# 03_-_Converter.net
KiCad netlist of a schematic drawn in Altium Designer
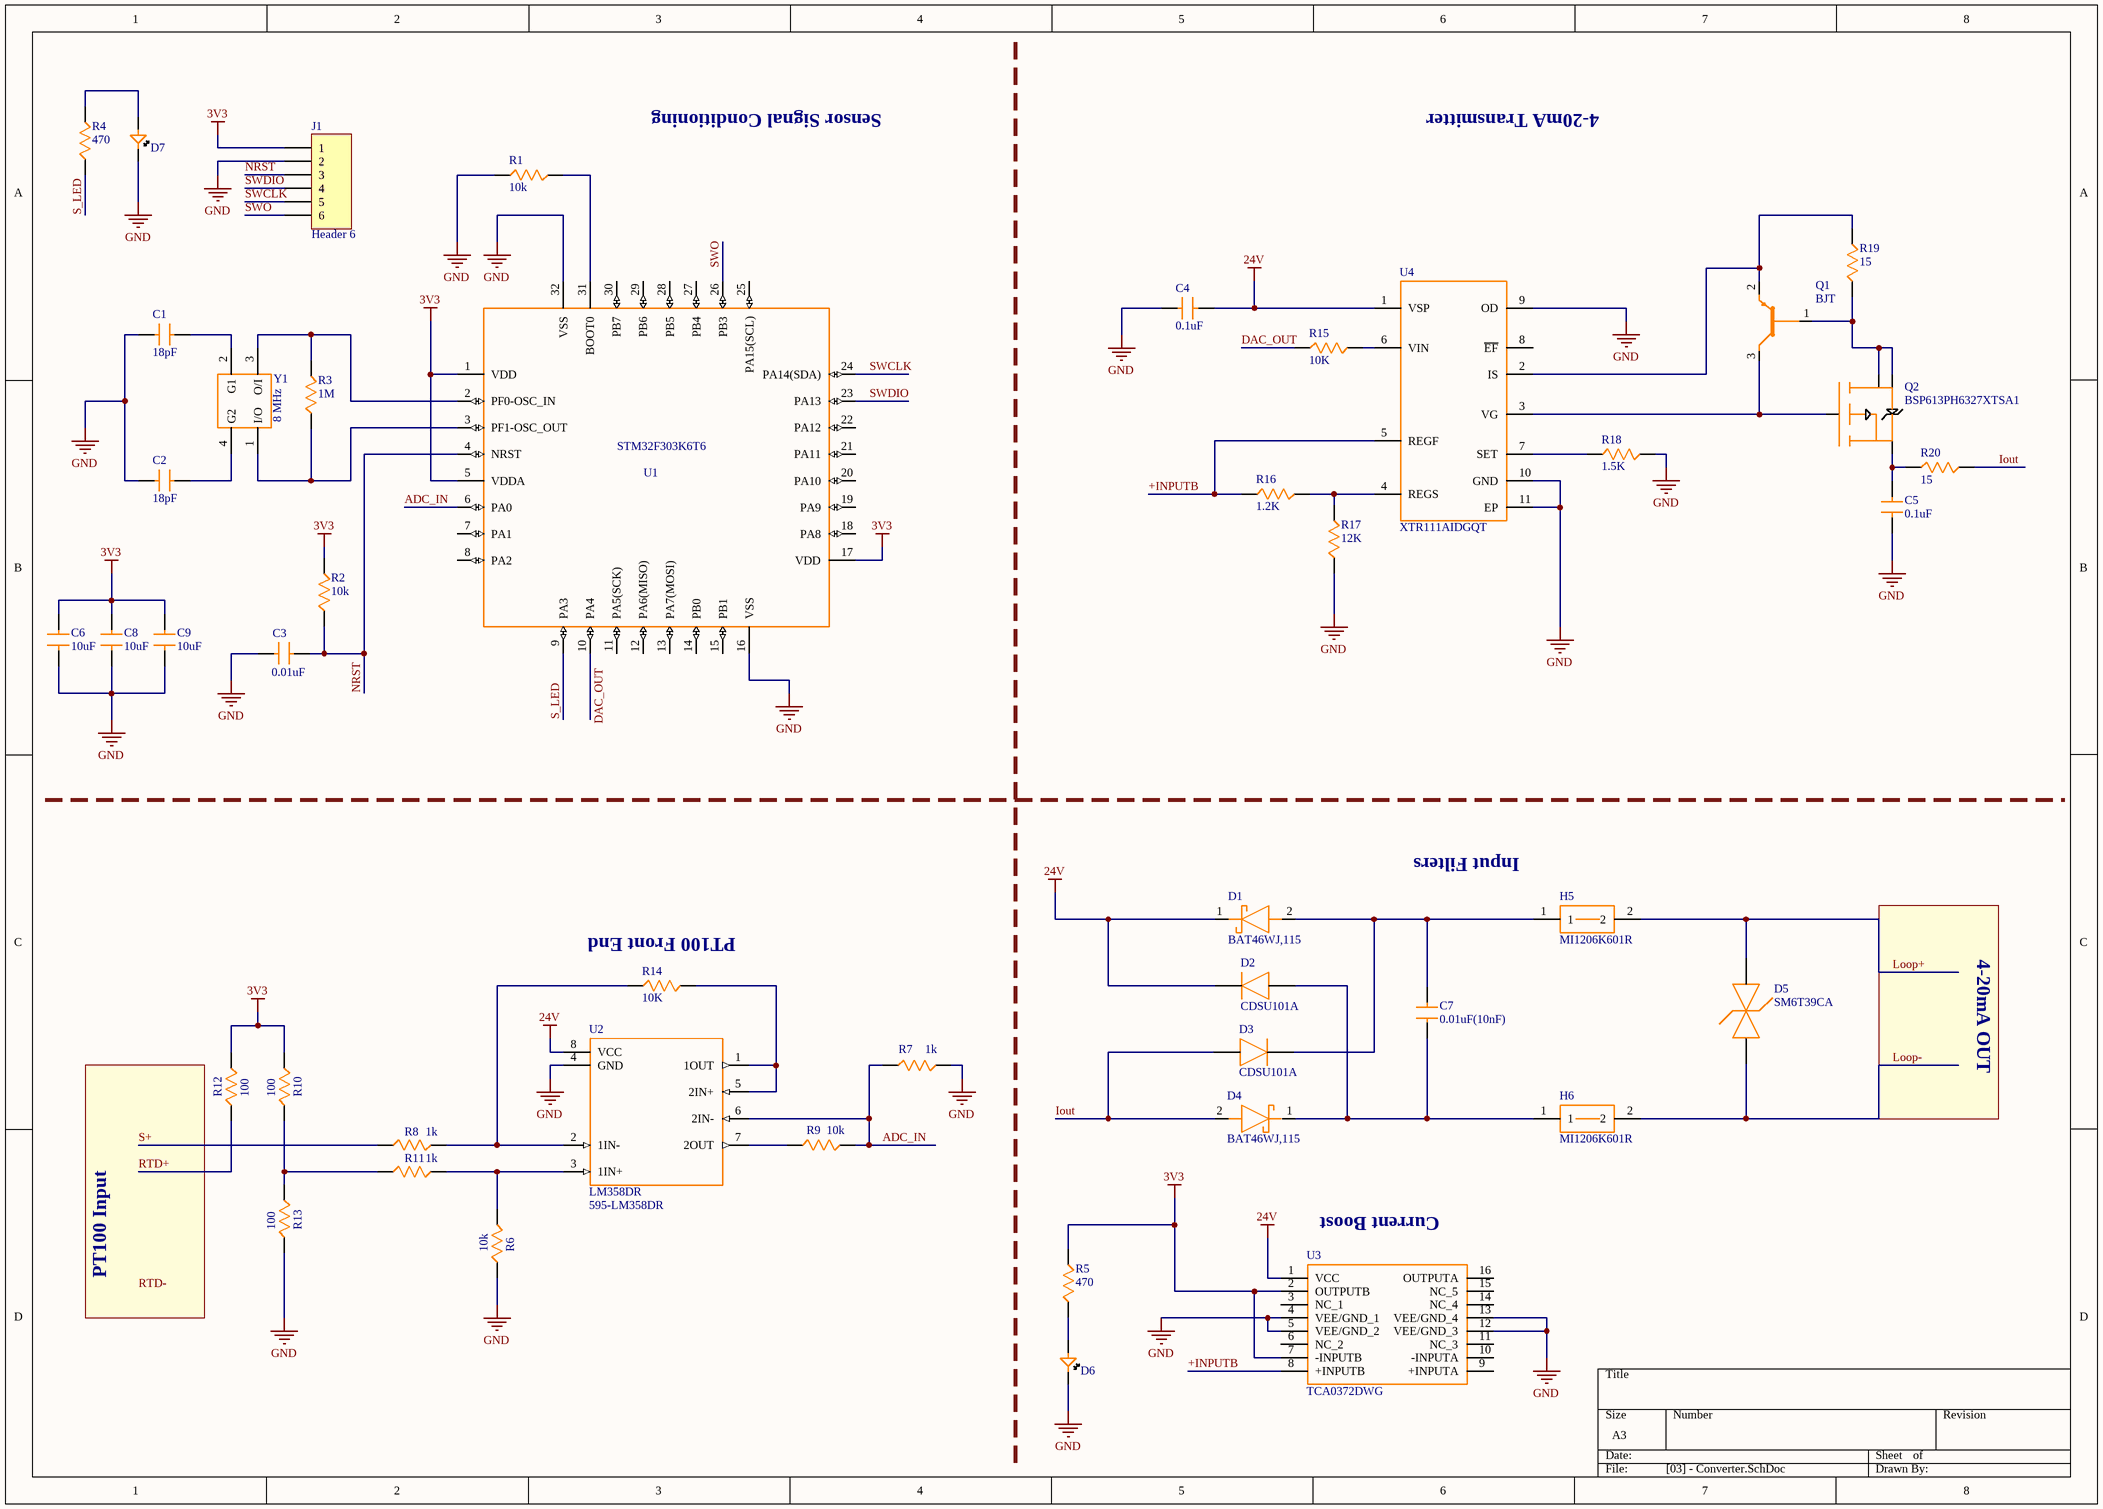
[diagram p0: [03] - Converter.SchDoc]

(export (version "E")
  (design (tool "Eeschema 10.0.6"))
  (components
    (comp (ref "C1")
      (value "18pF")
      (footprint "C0805")
      (description "Multilayer Ceramic Capacitors MLCC - SMD/SMT 0805 18pF 10volts C0G 10%")
      (fields
        (field (name "MANUFACTURER") "Vishay / Vitramon")
        (field (name "MANUFACTURER PART NUMBER") "VJ0805A180KXQPW1BC")
      )
      (libsource (lib "Joule_Library") (part "VJ0805A180KXQPW1BC"))
    )
    (comp (ref "C2")
      (value "18pF")
      (footprint "C0805")
      (description "Multilayer Ceramic Capacitors MLCC - SMD/SMT 0805 18pF 10volts C0G 10%")
      (fields
        (field (name "MANUFACTURER") "Vishay / Vitramon")
        (field (name "MANUFACTURER PART NUMBER") "VJ0805A180KXQPW1BC")
      )
      (libsource (lib "Joule_Library") (part "VJ0805A180KXQPW1BC"))
    )
    (comp (ref "C3")
      (value "0.01uF")
      (footprint "C0805")
      (description "Multilayer Ceramic Capacitors MLCC - SMD/SMT 0.01uF 10% 50V AEC-Q200")
      (fields
        (field (name "MANUFACTURER") "Yageo")
        (field (name "MANUFACTURER PART NUMBER") "AS0805KRX7R9BB103")
      )
      (libsource (lib "Joule_Library") (part "AS0805KRX7R9BB103"))
    )
    (comp (ref "C4")
      (value "0.1uF")
      (footprint "C0805")
      (description "Multilayer Ceramic Capacitors MLCC - SMD/SMT 0.1uF 10% 50V AEC-Q200")
      (fields
        (field (name "MANUFACTURER") "Yageo")
        (field (name "MANUFACTURER PART NUMBER") "AS0805KKX7R9BB104")
      )
      (libsource (lib "Joule_Library") (part "AS0805KKX7R9BB104"))
    )
    (comp (ref "C5")
      (value "0.1uF")
      (footprint "C0805")
      (description "Multilayer Ceramic Capacitors MLCC - SMD/SMT 0.1uF 10% 50V AEC-Q200")
      (fields
        (field (name "MANUFACTURER") "Yageo")
        (field (name "MANUFACTURER PART NUMBER") "AS0805KKX7R9BB104")
      )
      (libsource (lib "Joule_Library") (part "AS0805KKX7R9BB104"))
    )
    (comp (ref "C6")
      (value "10uF")
      (footprint "C0805")
      (description "Multilayer Ceramic Capacitors MLCC - SMD/SMT 10V 10uF 0603 X5R 20%")
      (fields
        (field (name "MANUFACTURER") "KEMET")
        (field (name "MANUFACTURER PART NUMBER") "C0603C106M8PACTU")
      )
      (libsource (lib "Joule_Library") (part "C0603C106M8PACTU"))
    )
    (comp (ref "C7")
      (value "0.01uF(10nF)")
      (footprint "PCBComponent_1")
      (description "Multilayer Ceramic Capacitors MLCC - SMD/SMT 100V 0.01uF C0G 0805 10% AEC-Q200")
      (fields
        (field (name "MANUFACTURER") "KEMET")
        (field (name "MANUFACTURER PART NUMBER") "C0805X103K1GECAUTO")
      )
      (libsource (lib "Joule_Library") (part "C0805X103K1GECAUTO"))
    )
    (comp (ref "C8")
      (value "10uF")
      (footprint "C0805")
      (description "Multilayer Ceramic Capacitors MLCC - SMD/SMT 10V 10uF 0603 X5R 20%")
      (fields
        (field (name "MANUFACTURER") "KEMET")
        (field (name "MANUFACTURER PART NUMBER") "C0603C106M8PACTU")
      )
      (libsource (lib "Joule_Library") (part "C0603C106M8PACTU"))
    )
    (comp (ref "C9")
      (value "10uF")
      (footprint "C0805")
      (description "Multilayer Ceramic Capacitors MLCC - SMD/SMT 10V 10uF 0603 X5R 20%")
      (fields
        (field (name "MANUFACTURER") "KEMET")
        (field (name "MANUFACTURER PART NUMBER") "C0603C106M8PACTU")
      )
      (libsource (lib "Joule_Library") (part "C0603C106M8PACTU"))
    )
    (comp (ref "D1")
      (value "BAT46WJ,115")
      (footprint "Diode:BAT46WJ,115")
      (description "Schottky Diodes & Rectifiers Schottky Diodes 100V 250mA Single")
      (fields (field (name "MANUFACTURER") "Nexperia"))
      (libsource (lib "Joule_Library") (part "BAT46WJ,115"))
    )
    (comp (ref "D2")
      (value "CDSU101A")
      (footprint "Diode:CDSU101A")
      (description "Diodes - General Purpose, Power, Switching 100mA 80V Sm Sgnl Switching")
      (fields (field (name "MANUFACTURER") "Comchip Technology"))
      (libsource (lib "Joule_Library") (part "CDSU101A"))
    )
    (comp (ref "D3")
      (value "CDSU101A")
      (footprint "Diode:CDSU101A")
      (description "Diodes - General Purpose, Power, Switching 100mA 80V Sm Sgnl Switching")
      (fields (field (name "MANUFACTURER") "Comchip Technology"))
      (libsource (lib "Joule_Library") (part "CDSU101A"))
    )
    (comp (ref "D4")
      (value "BAT46WJ,115")
      (footprint "Diode:BAT46WJ,115")
      (description "Schottky Diodes & Rectifiers Schottky Diodes 100V 250mA Single")
      (fields (field (name "MANUFACTURER") "Nexperia"))
      (libsource (lib "Joule_Library") (part "BAT46WJ,115"))
    )
    (comp (ref "D5")
      (value "SM6T39CA")
      (footprint "SM6T39CA")
      (description "ESD Suppressors / TVS Diodes 600W 39V Bidirect")
      (fields (field (name "MANUFACTURER") "STMicroelectronics"))
      (libsource (lib "Joule_Library") (part "SM6T39CA"))
    )
    (comp (ref "D6")
      (value "599-0130-007F")
      (footprint "LED0805")
      (description "Standard LEDs - SMD SMD 0805 ORANGE")
      (fields (field (name "MANUFACTURER") "Dialight"))
      (libsource (lib "Joule_Library") (part "599-0130-007F"))
    )
    (comp (ref "D7")
      (value "599-0130-007F")
      (footprint "LED0805")
      (description "Standard LEDs - SMD SMD 0805 ORANGE")
      (fields (field (name "MANUFACTURER") "Dialight"))
      (libsource (lib "Joule_Library") (part "599-0130-007F"))
    )
    (comp (ref "H5")
      (value "MI1206K601R")
      (footprint "Diode:MI1206K601R")
      (description "Ferrite Beads 600ohms 100MHz 1.5A Monolithic 1206 SMD")
      (fields
        (field (name "MANUFACTURER") "Laird")
        (field (name "MANUFACTURER PART NUMBER") "MI1206K601R-10")
      )
      (libsource (lib "Joule_Library") (part "MI1206K601R-10"))
    )
    (comp (ref "H6")
      (value "MI1206K601R")
      (footprint "Diode:MI1206K601R")
      (description "Ferrite Beads 600ohms 100MHz 1.5A Monolithic 1206 SMD")
      (fields
        (field (name "MANUFACTURER") "Laird")
        (field (name "MANUFACTURER PART NUMBER") "MI1206K601R-10")
      )
      (libsource (lib "Joule_Library") (part "MI1206K601R-10"))
    )
    (comp (ref "J1")
      (value "Header 6")
      (footprint "HDR1X6")
      (description "Header, 6-Pin")
      (fields (field (name "PUBLISHER") "Altium Limited"))
      (libsource (lib "Miscellaneous Connectors") (part "Header 6"))
    )
    (comp (ref "Q1")
      (value "BJT")
      (footprint "SMMBT2907ALT3G")
      (description "Bipolar Transistors - BJT SS GP XSTR SPCL TR")
      (fields
        (field (name "MANUFACTURER") "ON Semiconductor")
        (field (name "MANUFACTURER PART NUMBER") "SMMBT2907ALT3G")
      )
      (libsource (lib "Joule_Library") (part "SMMBT2907ALT3G"))
    )
    (comp (ref "Q2")
      (value "BSP613PH6327XTSA1")
      (footprint "BSP613PH6327XTA1")
      (description "MOSFET P-Ch -60V -2.9A SOT-223-3")
      (fields (field (name "MANUFACTURER") "Infineon Technologies"))
      (libsource (lib "Converter_Module_PT100_V2l1") (part "BSP613PH6327XTSA1"))
    )
    (comp (ref "R1")
      (value "10k")
      (footprint "R0805")
      (description "Thin Film Resistors - SMD 10K ohm 1% 1/10W")
      (fields
        (field (name "MANUFACTURER") "Yageo")
        (field (name "MANUFACTURER PART NUMBER") "RT0603FRE0710KL")
      )
      (libsource (lib "Joule_Library") (part "RT0603FRE0710KL"))
    )
    (comp (ref "R2")
      (value "10k")
      (footprint "R0805")
      (description "Thin Film Resistors - SMD 10K ohm 1% 1/10W")
      (fields
        (field (name "MANUFACTURER") "Yageo")
        (field (name "MANUFACTURER PART NUMBER") "RT0603FRE0710KL")
      )
      (libsource (lib "Joule_Library") (part "RT0603FRE0710KL"))
    )
    (comp (ref "R3")
      (value "1M")
      (footprint "R0805")
      (description "Thin Film Resistors - SMD 1 Mohm 0.5% Tol. AEC-Q200")
      (fields
        (field (name "MANUFACTURER") "Yageo")
        (field (name "MANUFACTURER PART NUMBER") "AT0805DRD071ML")
      )
      (libsource (lib "Joule_Library") (part "AT0805DRD071ML"))
    )
    (comp (ref "R4")
      (value "470")
      (footprint "R0805")
      (description "Thin Film Resistors - SMD 1/10W 470 ohm 1% 50ppm")
      (fields
        (field (name "MANUFACTURER") "Yageo")
        (field (name "MANUFACTURER PART NUMBER") "RT0603FRE07470RL")
      )
      (libsource (lib "Joule_Library") (part "RT0603FRE07470RL"))
    )
    (comp (ref "R5")
      (value "470")
      (footprint "R0805")
      (description "Thin Film Resistors - SMD 1/10W 470 ohm 1% 50ppm")
      (fields
        (field (name "MANUFACTURER") "Yageo")
        (field (name "MANUFACTURER PART NUMBER") "RT0603FRE07470RL")
      )
      (libsource (lib "Joule_Library") (part "RT0603FRE07470RL"))
    )
    (comp (ref "R6")
      (value "10k")
      (footprint "R0805")
      (description "Thin Film Resistors - SMD 10K ohm 1% 1/10W")
      (fields
        (field (name "MANUFACTURER") "Yageo")
        (field (name "MANUFACTURER PART NUMBER") "RT0603FRE0710KL")
      )
      (libsource (lib "Joule_Library") (part "RT0603FRE0710KL"))
    )
    (comp (ref "R7")
      (value "1k")
      (footprint "R0805")
      (description "Thin Film Resistors - SMD 1K ohm 1% 1/10W")
      (fields
        (field (name "MANUFACTURER") "Yageo")
        (field (name "MANUFACTURER PART NUMBER") "RT0603FRE071KL")
      )
      (libsource (lib "Joule_Library") (part "RT0603FRE071KL"))
    )
    (comp (ref "R8")
      (value "1k")
      (footprint "R0805")
      (description "Thin Film Resistors - SMD 1K ohm 1% 1/10W")
      (fields
        (field (name "MANUFACTURER") "Yageo")
        (field (name "MANUFACTURER PART NUMBER") "RT0603FRE071KL")
      )
      (libsource (lib "Joule_Library") (part "RT0603FRE071KL"))
    )
    (comp (ref "R9")
      (value "10k")
      (footprint "R0805")
      (description "Thin Film Resistors - SMD 10K ohm 1% 1/10W")
      (fields
        (field (name "MANUFACTURER") "Yageo")
        (field (name "MANUFACTURER PART NUMBER") "RT0603FRE0710KL")
      )
      (libsource (lib "Joule_Library") (part "RT0603FRE0710KL"))
    )
    (comp (ref "R10")
      (value "100")
      (footprint "R0805")
      (description "Thin Film Resistors - SMD 1/10W 100 ohm 1% 50ppm")
      (fields
        (field (name "MANUFACTURER") "Yageo")
        (field (name "MANUFACTURER PART NUMBER") "RT0603FRE07100RL")
      )
      (libsource (lib "Joule_Library") (part "RT0603FRE07100RL"))
    )
    (comp (ref "R11")
      (value "1k")
      (footprint "R0805")
      (description "Thin Film Resistors - SMD 1K ohm 1% 1/10W")
      (fields
        (field (name "MANUFACTURER") "Yageo")
        (field (name "MANUFACTURER PART NUMBER") "RT0603FRE071KL")
      )
      (libsource (lib "Joule_Library") (part "RT0603FRE071KL"))
    )
    (comp (ref "R12")
      (value "100")
      (footprint "R0805")
      (description "Thin Film Resistors - SMD 1/10W 100 ohm 1% 50ppm")
      (fields
        (field (name "MANUFACTURER") "Yageo")
        (field (name "MANUFACTURER PART NUMBER") "RT0603FRE07100RL")
      )
      (libsource (lib "Joule_Library") (part "RT0603FRE07100RL"))
    )
    (comp (ref "R13")
      (value "100")
      (footprint "R0805")
      (description "Thin Film Resistors - SMD 1/10W 100 ohm 1% 50ppm")
      (fields
        (field (name "MANUFACTURER") "Yageo")
        (field (name "MANUFACTURER PART NUMBER") "RT0603FRE07100RL")
      )
      (libsource (lib "Joule_Library") (part "RT0603FRE07100RL"))
    )
    (comp (ref "R14")
      (value "10K")
      (footprint "R0805")
      (description "Thick Film Resistors - SMD 10K   OHM   1% 1/4W")
      (fields
        (field (name "MANUFACTURER") "Yageo")
        (field (name "MANUFACTURER PART NUMBER") "RC0805FR-7W10KL")
      )
      (libsource (lib "Joule_Library") (part "RC0805FR-7W10KL"))
    )
    (comp (ref "R15")
      (value "10K")
      (footprint "R0805")
      (description "Thick Film Resistors - SMD 10K   OHM   1% 1/4W")
      (fields
        (field (name "MANUFACTURER") "Yageo")
        (field (name "MANUFACTURER PART NUMBER") "RC0805FR-7W10KL")
      )
      (libsource (lib "Joule_Library") (part "RC0805FR-7W10KL"))
    )
    (comp (ref "R16")
      (value "1.2K")
      (footprint "R0805")
      (description "Thick Film Resistors - SMD 0.4watt 1.2Kohms 1% 100ppm")
      (fields
        (field (name "MANUFACTURER") "Vishay")
        (field (name "MANUFACTURER PART NUMBER") "RCS08051K20FKEA")
      )
      (libsource (lib "Joule_Library") (part "RCS08051K20FKEA"))
    )
    (comp (ref "R17")
      (value "12K")
      (footprint "R0805")
      (description "Thick Film Resistors - SMD 12K OHM 1%")
      (fields
        (field (name "MANUFACTURER") "Yageo")
        (field (name "MANUFACTURER PART NUMBER") "RC0805FR-0712KL")
      )
      (libsource (lib "Joule_Library") (part "RC0805FR-0712KL"))
    )
    (comp (ref "R18")
      (value "1.5K")
      (footprint "R0805")
      (description "Thin Film Resistors - SMD 1.5K ohm 1% 50 ppm Thin Film")
      (fields
        (field (name "MANUFACTURER") "Yageo")
        (field (name "MANUFACTURER PART NUMBER") "RT0805FRE101K5L")
      )
      (libsource (lib "Joule_Library") (part "RT0805FRE101K5L"))
    )
    (comp (ref "R19")
      (value "15")
      (footprint "R0805")
      (description "Thin Film Resistors - SMD 15 Ohms 0.1% Tol. AEC-Q200")
      (fields
        (field (name "MANUFACTURER") "Yageo")
        (field (name "MANUFACTURER PART NUMBER") "AT0805BRD0715RL")
      )
      (libsource (lib "Joule_Library") (part "AT0805BRD0715RL"))
    )
    (comp (ref "R20")
      (value "15")
      (footprint "R0805")
      (description "Thin Film Resistors - SMD 15 Ohms 0.1% Tol. AEC-Q200")
      (fields
        (field (name "MANUFACTURER") "Yageo")
        (field (name "MANUFACTURER PART NUMBER") "AT0805BRD0715RL")
      )
      (libsource (lib "Joule_Library") (part "AT0805BRD0715RL"))
    )
    (comp (ref "U1")
      (value "STM32F303K6T6")
      (footprint "STM32F303K6T6")
      (description "ARM Microcontrollers - MCU 16/32-BITS MICROS")
      (fields (field (name "MANUFACTURER") "STMicroelectronics"))
      (libsource (lib "Integrated_Library") (part "STM32F303K6T6"))
    )
    (comp (ref "U2")
      (value "LM358DR")
      (footprint "LM358DR")
      (description "Operational Amplifiers - Op Amps Dual Op Amp")
      (fields
        (field (name "MANUFACTURER") "Texas Instruments")
        (field (name "SUPPLIER PART NUMBER 1") "595-LM358DR")
      )
      (libsource (lib "LM358DR_sch") (part "LM358DR"))
    )
    (comp (ref "U3")
      (value "TCA0372DWG")
      (footprint "TCA0372DWG")
      (description "Operational Amplifiers - Op Amps 5-40V 1A Output Extended Temp")
      (fields (field (name "MANUFACTURER") "ON Semiconductor"))
      (libsource (lib "TCA0372DWG_sch") (part "TCA0372DWG"))
    )
    (comp (ref "U4")
      (value "XTR111AIDGQT")
      (footprint "XTR111AIDGQT_pcb:XTR111AIDGQT")
      (description "Sensor Interface Prec Vltg-to-Crnt Conv/Transmitter")
      (fields (field (name "MANUFACTURER") "Texas Instruments"))
      (libsource (lib "XTR111AIDGQT_sch") (part "XTR111AIDGQT"))
    )
    (comp (ref "Y1")
      (value "8 MHz")
      (footprint "ECS-80-18-30B-AGN")
      (description "Crystals 8MHz 25ppm 18pF -40C +85C")
      (fields
        (field (name "MANUFACTURER") "ECS")
        (field (name "MANUFACTURER PART NUMBER") "ECS-80-18-30B-AGN-TR")
      )
      (libsource (lib "Converter_Module_PT100_V2l1_temp") (part "ECS-80-18-30B-AGN-TR"))
    )
  )
  (nets
    (net (code "1") (name "/+INPUTB") (class "Default")
      (node (ref "R16") (pin "1") (pinfunction "1_1") (pintype "passive"))
      (node (ref "U3") (pin "8") (pinfunction "+INPUTB_8") (pintype "passive"))
      (node (ref "U4") (pin "5") (pinfunction "REGF_5") (pintype "passive"))
    )
    (net (code "2") (name "/ADC_IN") (class "Default")
      (node (ref "R7") (pin "1") (pinfunction "1_1") (pintype "passive"))
      (node (ref "R9") (pin "1") (pinfunction "1_1") (pintype "passive"))
      (node (ref "U1") (pin "6") (pinfunction "PA0_6") (pintype "bidirectional"))
      (node (ref "U2") (pin "6") (pinfunction "2IN-_6") (pintype "input"))
    )
    (net (code "3") (name "/DAC_OUT") (class "Default")
      (node (ref "R15") (pin "2") (pinfunction "2_2") (pintype "passive"))
      (node (ref "U1") (pin "10") (pinfunction "PA4_10") (pintype "bidirectional"))
    )
    (net (code "4") (name "/Iout") (class "Default")
      (node (ref "D3") (pin "2") (pinfunction "A_2") (pintype "passive"))
      (node (ref "D4") (pin "2") (pinfunction "A_2") (pintype "passive"))
      (node (ref "R20") (pin "1") (pinfunction "1_1") (pintype "passive"))
    )
    (net (code "5") (name "/Loop+") (class "Default")
      (node (ref "D5") (pin "2") (pinfunction "A_2") (pintype "passive"))
      (node (ref "H5") (pin "2") (pinfunction "2_2") (pintype "passive"))
    )
    (net (code "6") (name "/Loop-") (class "Default")
      (node (ref "D5") (pin "1") (pinfunction "K_1") (pintype "passive"))
      (node (ref "H6") (pin "2") (pinfunction "2_2") (pintype "passive"))
    )
    (net (code "7") (name "/NRST") (class "Default")
      (node (ref "C3") (pin "2") (pinfunction "2_2") (pintype "passive"))
      (node (ref "J1") (pin "3") (pinfunction "3_3") (pintype "passive"))
      (node (ref "R2") (pin "2") (pinfunction "2_2") (pintype "passive"))
      (node (ref "U1") (pin "4") (pinfunction "NRST_4") (pintype "bidirectional"))
    )
    (net (code "8") (name "/RTD+") (class "Default")
      (node (ref "R12") (pin "1") (pinfunction "1_1") (pintype "passive"))
    )
    (net (code "10") (name "/S+") (class "Default")
      (node (ref "R8") (pin "1") (pinfunction "1_1") (pintype "passive"))
    )
    (net (code "11") (name "/SWCLK") (class "Default")
      (node (ref "J1") (pin "5") (pinfunction "5_5") (pintype "passive"))
      (node (ref "U1") (pin "24") (pinfunction "PA14(SDA)_24") (pintype "bidirectional"))
    )
    (net (code "12") (name "/SWDIO") (class "Default")
      (node (ref "J1") (pin "4") (pinfunction "4_4") (pintype "passive"))
      (node (ref "U1") (pin "23") (pinfunction "PA13_23") (pintype "bidirectional"))
    )
    (net (code "13") (name "/SWO") (class "Default")
      (node (ref "J1") (pin "6") (pinfunction "6_6") (pintype "passive"))
      (node (ref "U1") (pin "26") (pinfunction "PB3_26") (pintype "bidirectional"))
    )
    (net (code "14") (name "/S_LED") (class "Default")
      (node (ref "R4") (pin "1") (pinfunction "1_1") (pintype "passive"))
      (node (ref "U1") (pin "9") (pinfunction "PA3_9") (pintype "bidirectional"))
    )
    (net (code "15") (name "3V3") (class "Default")
      (node (ref "C6") (pin "2") (pinfunction "2_2") (pintype "passive"))
      (node (ref "C8") (pin "2") (pinfunction "2_2") (pintype "passive"))
      (node (ref "C9") (pin "2") (pinfunction "2_2") (pintype "passive"))
      (node (ref "J1") (pin "1") (pinfunction "1_1") (pintype "passive"))
      (node (ref "R10") (pin "2") (pinfunction "2_2") (pintype "passive"))
      (node (ref "R12") (pin "2") (pinfunction "2_2") (pintype "passive"))
      (node (ref "R2") (pin "1") (pinfunction "1_1") (pintype "passive"))
      (node (ref "R5") (pin "2") (pinfunction "2_2") (pintype "passive"))
      (node (ref "U1") (pin "1") (pinfunction "VDD_1") (pintype "power_in"))
      (node (ref "U1") (pin "17") (pinfunction "VDD_17") (pintype "power_in"))
      (node (ref "U1") (pin "5") (pinfunction "VDDA_5") (pintype "power_in"))
      (node (ref "U3") (pin "2") (pinfunction "OUTPUTB_2") (pintype "passive"))
      (node (ref "U3") (pin "7") (pinfunction "-INPUTB_7") (pintype "passive"))
    )
    (net (code "16") (name "24V") (class "Default")
      (node (ref "C4") (pin "1") (pinfunction "1_1") (pintype "passive"))
      (node (ref "D1") (pin "1") (pinfunction "K_1") (pintype "passive"))
      (node (ref "D2") (pin "1") (pinfunction "K_1") (pintype "passive"))
      (node (ref "U2") (pin "8") (pinfunction "VCC_8") (pintype "power_in"))
      (node (ref "U3") (pin "1") (pinfunction "VCC_1") (pintype "power_in"))
      (node (ref "U4") (pin "1") (pinfunction "VSP_1") (pintype "passive"))
    )
    (net (code "17") (name "GND") (class "Default")
      (node (ref "C1") (pin "1") (pinfunction "1_1") (pintype "passive"))
      (node (ref "C2") (pin "1") (pinfunction "1_1") (pintype "passive"))
      (node (ref "C3") (pin "1") (pinfunction "1_1") (pintype "passive"))
      (node (ref "C4") (pin "2") (pinfunction "2_2") (pintype "passive"))
      (node (ref "C5") (pin "1") (pinfunction "1_1") (pintype "passive"))
      (node (ref "C6") (pin "1") (pinfunction "1_1") (pintype "passive"))
      (node (ref "C8") (pin "1") (pinfunction "1_1") (pintype "passive"))
      (node (ref "C9") (pin "1") (pinfunction "1_1") (pintype "passive"))
      (node (ref "D6") (pin "2") (pinfunction "2_2") (pintype "passive"))
      (node (ref "D7") (pin "2") (pinfunction "2_2") (pintype "passive"))
      (node (ref "J1") (pin "2") (pinfunction "2_2") (pintype "passive"))
      (node (ref "R1") (pin "1") (pinfunction "1_1") (pintype "passive"))
      (node (ref "R13") (pin "1") (pinfunction "1_1") (pintype "passive"))
      (node (ref "R17") (pin "1") (pinfunction "1_1") (pintype "passive"))
      (node (ref "R18") (pin "2") (pinfunction "2_2") (pintype "passive"))
      (node (ref "R6") (pin "1") (pinfunction "1_1") (pintype "passive"))
      (node (ref "R7") (pin "2") (pinfunction "2_2") (pintype "passive"))
      (node (ref "U1") (pin "16") (pinfunction "VSS_16") (pintype "power_in"))
      (node (ref "U1") (pin "32") (pinfunction "VSS_32") (pintype "power_in"))
      (node (ref "U2") (pin "4") (pinfunction "GND_4") (pintype "passive"))
      (node (ref "U3") (pin "12") (pinfunction "VEE/GND_3_12") (pintype "passive"))
      (node (ref "U3") (pin "13") (pinfunction "VEE/GND_4_13") (pintype "passive"))
      (node (ref "U3") (pin "4") (pinfunction "VEE/GND_1_4") (pintype "passive"))
      (node (ref "U3") (pin "5") (pinfunction "VEE/GND_2_5") (pintype "passive"))
      (node (ref "U4") (pin "10") (pinfunction "GND_10") (pintype "passive"))
      (node (ref "U4") (pin "11") (pinfunction "EP_11") (pintype "passive"))
      (node (ref "U4") (pin "9") (pinfunction "OD_9") (pintype "passive"))
    )
    (net (code "18") (name "Net-(D1-A)") (class "Default")
      (node (ref "C7") (pin "2") (pinfunction "2_2") (pintype "passive"))
      (node (ref "D1") (pin "2") (pinfunction "A_2") (pintype "passive"))
      (node (ref "D3") (pin "1") (pinfunction "K_1") (pintype "passive"))
      (node (ref "H5") (pin "1") (pinfunction "1_1") (pintype "passive"))
    )
    (net (code "19") (name "Net-(D2-A)") (class "Default")
      (node (ref "C7") (pin "1") (pinfunction "1_1") (pintype "passive"))
      (node (ref "D2") (pin "2") (pinfunction "A_2") (pintype "passive"))
      (node (ref "D4") (pin "1") (pinfunction "K_1") (pintype "passive"))
      (node (ref "H6") (pin "1") (pinfunction "1_1") (pintype "passive"))
    )
    (net (code "20") (name "Net-(D6-Pad1)") (class "Default")
      (node (ref "D6") (pin "1") (pinfunction "1_1") (pintype "passive"))
      (node (ref "R5") (pin "1") (pinfunction "1_1") (pintype "passive"))
    )
    (net (code "21") (name "Net-(D7-Pad1)") (class "Default")
      (node (ref "D7") (pin "1") (pinfunction "1_1") (pintype "passive"))
      (node (ref "R4") (pin "2") (pinfunction "2_2") (pintype "passive"))
    )
    (net (code "22") (name "Net-(Q1-B)") (class "Default")
      (node (ref "Q1") (pin "1") (pinfunction "B_1") (pintype "passive"))
      (node (ref "Q2") (pin "2") (pinfunction "D@1_2") (pintype "passive"))
      (node (ref "Q2") (pin "4") (pinfunction "D@2_4") (pintype "passive"))
      (node (ref "R19") (pin "1") (pinfunction "1_1") (pintype "passive"))
    )
    (net (code "23") (name "Net-(Q1-C)") (class "Default")
      (node (ref "Q1") (pin "3") (pinfunction "C_3") (pintype "passive"))
      (node (ref "Q2") (pin "1") (pinfunction "G_1") (pintype "passive"))
      (node (ref "U4") (pin "3") (pinfunction "VG_3") (pintype "passive"))
    )
    (net (code "24") (name "Net-(Q1-E)") (class "Default")
      (node (ref "Q1") (pin "2") (pinfunction "E_2") (pintype "passive"))
      (node (ref "R19") (pin "2") (pinfunction "2_2") (pintype "passive"))
      (node (ref "U4") (pin "2") (pinfunction "IS_2") (pintype "passive"))
    )
    (net (code "25") (name "Net-(Q2-S)") (class "Default")
      (node (ref "C5") (pin "2") (pinfunction "2_2") (pintype "passive"))
      (node (ref "Q2") (pin "3") (pinfunction "S_3") (pintype "passive"))
      (node (ref "R20") (pin "2") (pinfunction "2_2") (pintype "passive"))
    )
    (net (code "26") (name "Net-(R10-Pad1)") (class "Default")
      (node (ref "R10") (pin "1") (pinfunction "1_1") (pintype "passive"))
      (node (ref "R11") (pin "1") (pinfunction "1_1") (pintype "passive"))
      (node (ref "R13") (pin "2") (pinfunction "2_2") (pintype "passive"))
    )
    (net (code "27") (name "Net-(U1-BOOT0)") (class "Default")
      (node (ref "R1") (pin "2") (pinfunction "2_2") (pintype "passive"))
      (node (ref "U1") (pin "31") (pinfunction "BOOT0_31") (pintype "passive"))
    )
    (net (code "28") (name "Net-(U1-PF0-OSC_IN)") (class "Default")
      (node (ref "R3") (pin "2") (pinfunction "2_2") (pintype "passive"))
      (node (ref "U1") (pin "2") (pinfunction "PF0-OSC_IN_2") (pintype "bidirectional"))
      (node (ref "Y1") (pin "3") (pinfunction "O/I_3") (pintype "passive"))
    )
    (net (code "29") (name "Net-(U1-PF1-OSC_OUT)") (class "Default")
      (node (ref "R3") (pin "1") (pinfunction "1_1") (pintype "passive"))
      (node (ref "U1") (pin "3") (pinfunction "PF1-OSC_OUT_3") (pintype "bidirectional"))
      (node (ref "Y1") (pin "1") (pinfunction "I/O_1") (pintype "passive"))
    )
    (net (code "30") (name "Net-(U2-1IN+)") (class "Default")
      (node (ref "R11") (pin "2") (pinfunction "2_2") (pintype "passive"))
      (node (ref "R6") (pin "2") (pinfunction "2_2") (pintype "passive"))
      (node (ref "U2") (pin "3") (pinfunction "1IN+_3") (pintype "input"))
    )
    (net (code "31") (name "Net-(U2-1IN-)") (class "Default")
      (node (ref "R14") (pin "1") (pinfunction "1_1") (pintype "passive"))
      (node (ref "R8") (pin "2") (pinfunction "2_2") (pintype "passive"))
      (node (ref "U2") (pin "2") (pinfunction "1IN-_2") (pintype "input"))
    )
    (net (code "32") (name "Net-(U2-1OUT)") (class "Default")
      (node (ref "R14") (pin "2") (pinfunction "2_2") (pintype "passive"))
      (node (ref "U2") (pin "1") (pinfunction "1OUT_1") (pintype "output"))
      (node (ref "U2") (pin "5") (pinfunction "2IN+_5") (pintype "input"))
    )
    (net (code "33") (name "Net-(U2-2OUT)") (class "Default")
      (node (ref "R9") (pin "2") (pinfunction "2_2") (pintype "passive"))
      (node (ref "U2") (pin "7") (pinfunction "2OUT_7") (pintype "output"))
    )
    (net (code "34") (name "Net-(U4-REGS)") (class "Default")
      (node (ref "R16") (pin "2") (pinfunction "2_2") (pintype "passive"))
      (node (ref "R17") (pin "2") (pinfunction "2_2") (pintype "passive"))
      (node (ref "U4") (pin "4") (pinfunction "REGS_4") (pintype "passive"))
    )
    (net (code "35") (name "Net-(U4-SET)") (class "Default")
      (node (ref "R18") (pin "1") (pinfunction "1_1") (pintype "passive"))
      (node (ref "U4") (pin "7") (pinfunction "SET_7") (pintype "passive"))
    )
    (net (code "36") (name "Net-(U4-VIN)") (class "Default")
      (node (ref "R15") (pin "1") (pinfunction "1_1") (pintype "passive"))
      (node (ref "U4") (pin "6") (pinfunction "VIN_6") (pintype "passive"))
    )
    (net (code "37") (name "Net-(Y1-G1)") (class "Default")
      (node (ref "C1") (pin "2") (pinfunction "2_2") (pintype "passive"))
      (node (ref "Y1") (pin "2") (pinfunction "G1_2") (pintype "passive"))
    )
    (net (code "38") (name "Net-(Y1-G2)") (class "Default")
      (node (ref "C2") (pin "2") (pinfunction "2_2") (pintype "passive"))
      (node (ref "Y1") (pin "4") (pinfunction "G2_4") (pintype "passive"))
    )
    (net (code "39") (name "unconnected-(U1-PA1-Pad7)") (class "Default")
      (node (ref "U1") (pin "7") (pinfunction "PA1_7") (pintype "bidirectional"))
    )
    (net (code "40") (name "unconnected-(U1-PA2-Pad8)") (class "Default")
      (node (ref "U1") (pin "8") (pinfunction "PA2_8") (pintype "bidirectional"))
    )
    (net (code "41") (name "unconnected-(U1-PA5(SCK)-Pad11)") (class "Default")
      (node (ref "U1") (pin "11") (pinfunction "PA5(SCK)_11") (pintype "bidirectional"))
    )
    (net (code "42") (name "unconnected-(U1-PA6(MISO)-Pad12)") (class "Default")
      (node (ref "U1") (pin "12") (pinfunction "PA6(MISO)_12") (pintype "bidirectional"))
    )
    (net (code "43") (name "unconnected-(U1-PA7(MOSI)-Pad13)") (class "Default")
      (node (ref "U1") (pin "13") (pinfunction "PA7(MOSI)_13") (pintype "bidirectional"))
    )
    (net (code "44") (name "unconnected-(U1-PA8-Pad18)") (class "Default")
      (node (ref "U1") (pin "18") (pinfunction "PA8_18") (pintype "bidirectional"))
    )
    (net (code "45") (name "unconnected-(U1-PA9-Pad19)") (class "Default")
      (node (ref "U1") (pin "19") (pinfunction "PA9_19") (pintype "bidirectional"))
    )
    (net (code "46") (name "unconnected-(U1-PA10-Pad20)") (class "Default")
      (node (ref "U1") (pin "20") (pinfunction "PA10_20") (pintype "bidirectional"))
    )
    (net (code "47") (name "unconnected-(U1-PA11-Pad21)") (class "Default")
      (node (ref "U1") (pin "21") (pinfunction "PA11_21") (pintype "bidirectional"))
    )
    (net (code "48") (name "unconnected-(U1-PA12-Pad22)") (class "Default")
      (node (ref "U1") (pin "22") (pinfunction "PA12_22") (pintype "bidirectional"))
    )
    (net (code "49") (name "unconnected-(U1-PA15(SCL)-Pad25)") (class "Default")
      (node (ref "U1") (pin "25") (pinfunction "PA15(SCL)_25") (pintype "bidirectional"))
    )
    (net (code "50") (name "unconnected-(U1-PB0-Pad14)") (class "Default")
      (node (ref "U1") (pin "14") (pinfunction "PB0_14") (pintype "bidirectional"))
    )
    (net (code "51") (name "unconnected-(U1-PB1-Pad15)") (class "Default")
      (node (ref "U1") (pin "15") (pinfunction "PB1_15") (pintype "bidirectional"))
    )
    (net (code "52") (name "unconnected-(U1-PB4-Pad27)") (class "Default")
      (node (ref "U1") (pin "27") (pinfunction "PB4_27") (pintype "bidirectional"))
    )
    (net (code "53") (name "unconnected-(U1-PB5-Pad28)") (class "Default")
      (node (ref "U1") (pin "28") (pinfunction "PB5_28") (pintype "bidirectional"))
    )
    (net (code "54") (name "unconnected-(U1-PB6-Pad29)") (class "Default")
      (node (ref "U1") (pin "29") (pinfunction "PB6_29") (pintype "bidirectional"))
    )
    (net (code "55") (name "unconnected-(U1-PB7-Pad30)") (class "Default")
      (node (ref "U1") (pin "30") (pinfunction "PB7_30") (pintype "bidirectional"))
    )
    (net (code "56") (name "unconnected-(U3-+INPUTA-Pad9)") (class "Default")
      (node (ref "U3") (pin "9") (pinfunction "+INPUTA_9") (pintype "passive"))
    )
    (net (code "57") (name "unconnected-(U3--INPUTA-Pad10)") (class "Default")
      (node (ref "U3") (pin "10") (pinfunction "-INPUTA_10") (pintype "passive"))
    )
    (net (code "58") (name "unconnected-(U3-NC_1-Pad3)") (class "Default")
      (node (ref "U3") (pin "3") (pinfunction "NC_1_3") (pintype "passive"))
    )
    (net (code "59") (name "unconnected-(U3-NC_2-Pad6)") (class "Default")
      (node (ref "U3") (pin "6") (pinfunction "NC_2_6") (pintype "passive"))
    )
    (net (code "60") (name "unconnected-(U3-NC_3-Pad11)") (class "Default")
      (node (ref "U3") (pin "11") (pinfunction "NC_3_11") (pintype "passive"))
    )
    (net (code "61") (name "unconnected-(U3-NC_4-Pad14)") (class "Default")
      (node (ref "U3") (pin "14") (pinfunction "NC_4_14") (pintype "passive"))
    )
    (net (code "62") (name "unconnected-(U3-NC_5-Pad15)") (class "Default")
      (node (ref "U3") (pin "15") (pinfunction "NC_5_15") (pintype "passive"))
    )
    (net (code "63") (name "unconnected-(U3-OUTPUTA-Pad16)") (class "Default")
      (node (ref "U3") (pin "16") (pinfunction "OUTPUTA_16") (pintype "passive"))
    )
    (net (code "64") (name "unconnected-(U4-EF-Pad8)") (class "Default")
      (node (ref "U4") (pin "8") (pinfunction "EF_8") (pintype "passive"))
    )
  )
)
